# Stm32-mez.net
KiCad netlist of a schematic drawn in EAGLE
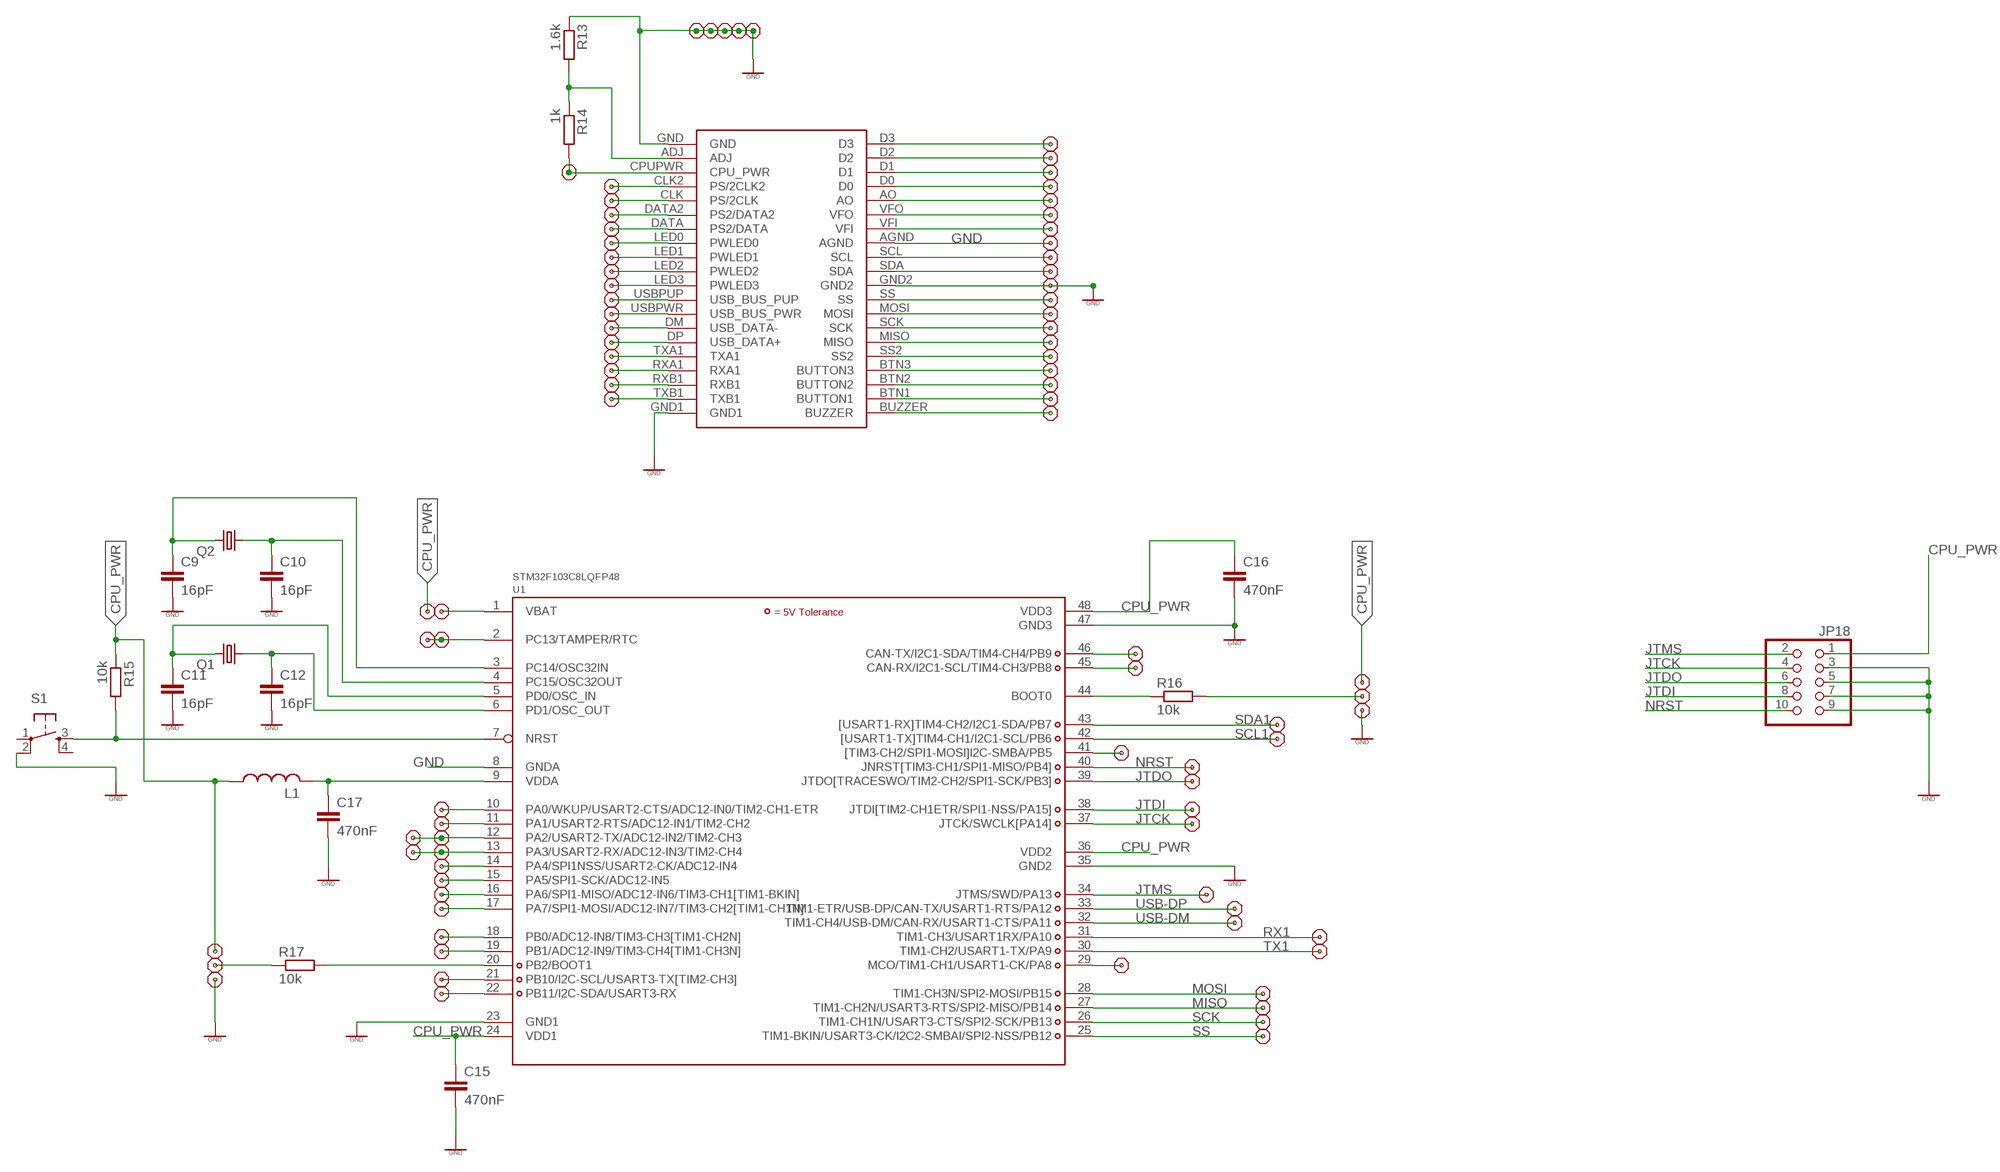
[diagram p0: schematic, sheet 1]

(export (version "E")
  (design (tool "Eeschema 10.0.6"))
  (components
    (comp (ref "C9")
      (value "16pF")
      (footprint "eagle-import:C1206")
      (libsource (lib "eagle-import") (part "C-EUC1206"))
    )
    (comp (ref "C10")
      (value "16pF")
      (footprint "eagle-import:C1206")
      (libsource (lib "eagle-import") (part "C-EUC1206"))
    )
    (comp (ref "C11")
      (value "16pF")
      (footprint "eagle-import:C1206")
      (libsource (lib "eagle-import") (part "C-EUC1206"))
    )
    (comp (ref "C12")
      (value "16pF")
      (footprint "eagle-import:C1206")
      (libsource (lib "eagle-import") (part "C-EUC1206"))
    )
    (comp (ref "C15")
      (value "470nF")
      (footprint "eagle-import:C1206")
      (libsource (lib "eagle-import") (part "C-EUC1206"))
    )
    (comp (ref "C16")
      (value "470nF")
      (footprint "eagle-import:C1206")
      (libsource (lib "eagle-import") (part "C-EUC1206"))
    )
    (comp (ref "C17")
      (value "470nF")
      (footprint "eagle-import:C1206")
      (libsource (lib "eagle-import") (part "C-EUC1206"))
    )
    (comp (ref "JP5")
      (value "PINHD-1X1PIN")
      (footprint "eagle-import:1X01")
      (libsource (lib "eagle-import") (part "PINHD-1X1PIN"))
    )
    (comp (ref "JP6")
      (value "PINHD-1X1PIN")
      (footprint "eagle-import:1X01")
      (libsource (lib "eagle-import") (part "PINHD-1X1PIN"))
    )
    (comp (ref "JP7")
      (value "PINHD-1X1PIN")
      (footprint "eagle-import:1X01")
      (libsource (lib "eagle-import") (part "PINHD-1X1PIN"))
    )
    (comp (ref "JP8")
      (value "PINHD-1X1PIN")
      (footprint "eagle-import:1X01")
      (libsource (lib "eagle-import") (part "PINHD-1X1PIN"))
    )
    (comp (ref "JP10")
      (value "PINHD-1X1PIN")
      (footprint "eagle-import:1X01")
      (libsource (lib "eagle-import") (part "PINHD-1X1PIN"))
    )
    (comp (ref "JP11")
      (value "PINHD-1X1PIN")
      (footprint "eagle-import:1X01")
      (libsource (lib "eagle-import") (part "PINHD-1X1PIN"))
    )
    (comp (ref "JP12")
      (value "PINHD-1X1PIN")
      (footprint "eagle-import:1X01")
      (libsource (lib "eagle-import") (part "PINHD-1X1PIN"))
    )
    (comp (ref "JP13")
      (value "PINHD-1X1PIN")
      (footprint "eagle-import:1X01")
      (libsource (lib "eagle-import") (part "PINHD-1X1PIN"))
    )
    (comp (ref "JP14")
      (value "PINHD-1X1PIN")
      (footprint "eagle-import:1X01")
      (libsource (lib "eagle-import") (part "PINHD-1X1PIN"))
    )
    (comp (ref "JP15")
      (value "PINHD-1X1PIN")
      (footprint "eagle-import:1X01")
      (libsource (lib "eagle-import") (part "PINHD-1X1PIN"))
    )
    (comp (ref "JP16")
      (value "PINHD-1X1PIN")
      (footprint "eagle-import:1X01")
      (libsource (lib "eagle-import") (part "PINHD-1X1PIN"))
    )
    (comp (ref "JP17")
      (value "PINHD-1X1PIN")
      (footprint "eagle-import:1X01")
      (libsource (lib "eagle-import") (part "PINHD-1X1PIN"))
    )
    (comp (ref "JP18")
      (value "PINHD-2X5")
      (footprint "eagle-import:2X05")
      (libsource (lib "eagle-import") (part "PINHD-2X5"))
    )
    (comp (ref "JP19")
      (value "PINHD-1X1PIN")
      (footprint "eagle-import:1X01")
      (libsource (lib "eagle-import") (part "PINHD-1X1PIN"))
    )
    (comp (ref "JP20")
      (value "PINHD-1X1PIN")
      (footprint "eagle-import:1X01")
      (libsource (lib "eagle-import") (part "PINHD-1X1PIN"))
    )
    (comp (ref "JP21")
      (value "PINHD-1X1PIN")
      (footprint "eagle-import:1X01")
      (libsource (lib "eagle-import") (part "PINHD-1X1PIN"))
    )
    (comp (ref "JP22")
      (value "PINHD-1X1PIN")
      (footprint "eagle-import:1X01")
      (libsource (lib "eagle-import") (part "PINHD-1X1PIN"))
    )
    (comp (ref "JP23")
      (value "PINHD-1X1PIN")
      (footprint "eagle-import:1X01")
      (libsource (lib "eagle-import") (part "PINHD-1X1PIN"))
    )
    (comp (ref "JP24")
      (value "PINHD-1X1PIN")
      (footprint "eagle-import:1X01")
      (libsource (lib "eagle-import") (part "PINHD-1X1PIN"))
    )
    (comp (ref "JP25")
      (value "PINHD-1X1PIN")
      (footprint "eagle-import:1X01")
      (libsource (lib "eagle-import") (part "PINHD-1X1PIN"))
    )
    (comp (ref "JP26")
      (value "PINHD-1X1PIN")
      (footprint "eagle-import:1X01")
      (libsource (lib "eagle-import") (part "PINHD-1X1PIN"))
    )
    (comp (ref "JP27")
      (value "PINHD-1X1PIN")
      (footprint "eagle-import:1X01")
      (libsource (lib "eagle-import") (part "PINHD-1X1PIN"))
    )
    (comp (ref "JP28")
      (value "PINHD-1X1PIN")
      (footprint "eagle-import:1X01")
      (libsource (lib "eagle-import") (part "PINHD-1X1PIN"))
    )
    (comp (ref "JP29")
      (value "PINHD-1X1PIN")
      (footprint "eagle-import:1X01")
      (libsource (lib "eagle-import") (part "PINHD-1X1PIN"))
    )
    (comp (ref "JP30")
      (value "PINHD-1X1PIN")
      (footprint "eagle-import:1X01")
      (libsource (lib "eagle-import") (part "PINHD-1X1PIN"))
    )
    (comp (ref "JP31")
      (value "PINHD-1X1PIN")
      (footprint "eagle-import:1X01")
      (libsource (lib "eagle-import") (part "PINHD-1X1PIN"))
    )
    (comp (ref "JP32")
      (value "PINHD-1X1PIN")
      (footprint "eagle-import:1X01")
      (libsource (lib "eagle-import") (part "PINHD-1X1PIN"))
    )
    (comp (ref "JP33")
      (value "PINHD-1X1PIN")
      (footprint "eagle-import:1X01")
      (libsource (lib "eagle-import") (part "PINHD-1X1PIN"))
    )
    (comp (ref "JP34")
      (value "PINHD-1X1PIN")
      (footprint "eagle-import:1X01")
      (libsource (lib "eagle-import") (part "PINHD-1X1PIN"))
    )
    (comp (ref "JP35")
      (value "PINHD-1X1PIN")
      (footprint "eagle-import:1X01")
      (libsource (lib "eagle-import") (part "PINHD-1X1PIN"))
    )
    (comp (ref "JP36")
      (value "PINHD-1X1PIN")
      (footprint "eagle-import:1X01")
      (libsource (lib "eagle-import") (part "PINHD-1X1PIN"))
    )
    (comp (ref "JP37")
      (value "PINHD-1X1PIN")
      (footprint "eagle-import:1X01")
      (libsource (lib "eagle-import") (part "PINHD-1X1PIN"))
    )
    (comp (ref "JP38")
      (value "PINHD-1X1PIN")
      (footprint "eagle-import:1X01")
      (libsource (lib "eagle-import") (part "PINHD-1X1PIN"))
    )
    (comp (ref "JP39")
      (value "PINHD-1X1PIN")
      (footprint "eagle-import:1X01")
      (libsource (lib "eagle-import") (part "PINHD-1X1PIN"))
    )
    (comp (ref "JP40")
      (value "PINHD-1X1PIN")
      (footprint "eagle-import:1X01")
      (libsource (lib "eagle-import") (part "PINHD-1X1PIN"))
    )
    (comp (ref "JP41")
      (value "PINHD-1X1PIN")
      (footprint "eagle-import:1X01")
      (libsource (lib "eagle-import") (part "PINHD-1X1PIN"))
    )
    (comp (ref "JP42")
      (value "PINHD-1X1PIN")
      (footprint "eagle-import:1X01")
      (libsource (lib "eagle-import") (part "PINHD-1X1PIN"))
    )
    (comp (ref "JP43")
      (value "PINHD-1X1PIN")
      (footprint "eagle-import:1X01")
      (libsource (lib "eagle-import") (part "PINHD-1X1PIN"))
    )
    (comp (ref "JP44")
      (value "PINHD-1X1PIN")
      (footprint "eagle-import:1X01")
      (libsource (lib "eagle-import") (part "PINHD-1X1PIN"))
    )
    (comp (ref "JP45")
      (value "PINHD-1X1PIN")
      (footprint "eagle-import:1X01")
      (libsource (lib "eagle-import") (part "PINHD-1X1PIN"))
    )
    (comp (ref "JP46")
      (value "PINHD-1X1PIN")
      (footprint "eagle-import:1X01")
      (libsource (lib "eagle-import") (part "PINHD-1X1PIN"))
    )
    (comp (ref "JP47")
      (value "PINHD-1X1PIN")
      (footprint "eagle-import:1X01")
      (libsource (lib "eagle-import") (part "PINHD-1X1PIN"))
    )
    (comp (ref "JP48")
      (value "PINHD-1X1PIN")
      (footprint "eagle-import:1X01")
      (libsource (lib "eagle-import") (part "PINHD-1X1PIN"))
    )
    (comp (ref "JP49")
      (value "PINHD-1X1PIN")
      (footprint "eagle-import:1X01")
      (libsource (lib "eagle-import") (part "PINHD-1X1PIN"))
    )
    (comp (ref "JP50")
      (value "PINHD-1X1PIN")
      (footprint "eagle-import:1X01")
      (libsource (lib "eagle-import") (part "PINHD-1X1PIN"))
    )
    (comp (ref "JP51")
      (value "PINHD-1X1PIN")
      (footprint "eagle-import:1X01")
      (libsource (lib "eagle-import") (part "PINHD-1X1PIN"))
    )
    (comp (ref "JP52")
      (value "PINHD-1X1PIN")
      (footprint "eagle-import:1X01")
      (libsource (lib "eagle-import") (part "PINHD-1X1PIN"))
    )
    (comp (ref "JP53")
      (value "PINHD-1X1PIN")
      (footprint "eagle-import:1X01")
      (libsource (lib "eagle-import") (part "PINHD-1X1PIN"))
    )
    (comp (ref "JP54")
      (value "PINHD-1X1PIN")
      (footprint "eagle-import:1X01")
      (libsource (lib "eagle-import") (part "PINHD-1X1PIN"))
    )
    (comp (ref "JP55")
      (value "PINHD-1X1PIN")
      (footprint "eagle-import:1X01")
      (libsource (lib "eagle-import") (part "PINHD-1X1PIN"))
    )
    (comp (ref "JP56")
      (value "PINHD-1X1PIN")
      (footprint "eagle-import:1X01")
      (libsource (lib "eagle-import") (part "PINHD-1X1PIN"))
    )
    (comp (ref "JP57")
      (value "PINHD-1X1PIN")
      (footprint "eagle-import:1X01")
      (libsource (lib "eagle-import") (part "PINHD-1X1PIN"))
    )
    (comp (ref "JP58")
      (value "PINHD-1X1PIN")
      (footprint "eagle-import:1X01")
      (libsource (lib "eagle-import") (part "PINHD-1X1PIN"))
    )
    (comp (ref "JP59")
      (value "PINHD-1X1PIN")
      (footprint "eagle-import:1X01")
      (libsource (lib "eagle-import") (part "PINHD-1X1PIN"))
    )
    (comp (ref "JP60")
      (value "PINHD-1X1PIN")
      (footprint "eagle-import:1X01")
      (libsource (lib "eagle-import") (part "PINHD-1X1PIN"))
    )
    (comp (ref "JP61")
      (value "PINHD-1X1PIN")
      (footprint "eagle-import:1X01")
      (libsource (lib "eagle-import") (part "PINHD-1X1PIN"))
    )
    (comp (ref "JP62")
      (value "PINHD-1X1PIN")
      (footprint "eagle-import:1X01")
      (libsource (lib "eagle-import") (part "PINHD-1X1PIN"))
    )
    (comp (ref "JP63")
      (value "PINHD-1X1PIN")
      (footprint "eagle-import:1X01")
      (libsource (lib "eagle-import") (part "PINHD-1X1PIN"))
    )
    (comp (ref "JP64")
      (value "PINHD-1X1PIN")
      (footprint "eagle-import:1X01")
      (libsource (lib "eagle-import") (part "PINHD-1X1PIN"))
    )
    (comp (ref "JP65")
      (value "PINHD-1X1PIN")
      (footprint "eagle-import:1X01")
      (libsource (lib "eagle-import") (part "PINHD-1X1PIN"))
    )
    (comp (ref "JP66")
      (value "PINHD-1X1PIN")
      (footprint "eagle-import:1X01")
      (libsource (lib "eagle-import") (part "PINHD-1X1PIN"))
    )
    (comp (ref "JP67")
      (value "PINHD-1X1PIN")
      (footprint "eagle-import:1X01")
      (libsource (lib "eagle-import") (part "PINHD-1X1PIN"))
    )
    (comp (ref "JP68")
      (value "PINHD-1X1PIN")
      (footprint "eagle-import:1X01")
      (libsource (lib "eagle-import") (part "PINHD-1X1PIN"))
    )
    (comp (ref "JP69")
      (value "PINHD-1X1PIN")
      (footprint "eagle-import:1X01")
      (libsource (lib "eagle-import") (part "PINHD-1X1PIN"))
    )
    (comp (ref "JP70")
      (value "PINHD-1X1PIN")
      (footprint "eagle-import:1X01")
      (libsource (lib "eagle-import") (part "PINHD-1X1PIN"))
    )
    (comp (ref "JP71")
      (value "PINHD-1X1PIN")
      (footprint "eagle-import:1X01")
      (libsource (lib "eagle-import") (part "PINHD-1X1PIN"))
    )
    (comp (ref "JP72")
      (value "PINHD-1X1PIN")
      (footprint "eagle-import:1X01")
      (libsource (lib "eagle-import") (part "PINHD-1X1PIN"))
    )
    (comp (ref "JP73")
      (value "PINHD-1X1PIN")
      (footprint "eagle-import:1X01")
      (libsource (lib "eagle-import") (part "PINHD-1X1PIN"))
    )
    (comp (ref "JP74")
      (value "PINHD-1X1PIN")
      (footprint "eagle-import:1X01")
      (libsource (lib "eagle-import") (part "PINHD-1X1PIN"))
    )
    (comp (ref "JP75")
      (value "PINHD-1X1PIN")
      (footprint "eagle-import:1X01")
      (libsource (lib "eagle-import") (part "PINHD-1X1PIN"))
    )
    (comp (ref "JP76")
      (value "PINHD-1X1PIN")
      (footprint "eagle-import:1X01")
      (libsource (lib "eagle-import") (part "PINHD-1X1PIN"))
    )
    (comp (ref "JP77")
      (value "PINHD-1X1PIN")
      (footprint "eagle-import:1X01")
      (libsource (lib "eagle-import") (part "PINHD-1X1PIN"))
    )
    (comp (ref "JP78")
      (value "PINHD-1X1PIN")
      (footprint "eagle-import:1X01")
      (libsource (lib "eagle-import") (part "PINHD-1X1PIN"))
    )
    (comp (ref "JP79")
      (value "PINHD-1X1PIN")
      (footprint "eagle-import:1X01")
      (libsource (lib "eagle-import") (part "PINHD-1X1PIN"))
    )
    (comp (ref "JP80")
      (value "PINHD-1X1PIN")
      (footprint "eagle-import:1X01")
      (libsource (lib "eagle-import") (part "PINHD-1X1PIN"))
    )
    (comp (ref "JP81")
      (value "PINHD-1X1PIN")
      (footprint "eagle-import:1X01")
      (libsource (lib "eagle-import") (part "PINHD-1X1PIN"))
    )
    (comp (ref "JP82")
      (value "PINHD-1X1PIN")
      (footprint "eagle-import:1X01")
      (libsource (lib "eagle-import") (part "PINHD-1X1PIN"))
    )
    (comp (ref "JP83")
      (value "PINHD-1X1PIN")
      (footprint "eagle-import:1X01")
      (libsource (lib "eagle-import") (part "PINHD-1X1PIN"))
    )
    (comp (ref "JP84")
      (value "PINHD-1X1PIN")
      (footprint "eagle-import:1X01")
      (libsource (lib "eagle-import") (part "PINHD-1X1PIN"))
    )
    (comp (ref "JP85")
      (value "PINHD-1X1PIN")
      (footprint "eagle-import:1X01")
      (libsource (lib "eagle-import") (part "PINHD-1X1PIN"))
    )
    (comp (ref "JP86")
      (value "PINHD-1X1PIN")
      (footprint "eagle-import:1X01")
      (libsource (lib "eagle-import") (part "PINHD-1X1PIN"))
    )
    (comp (ref "JP87")
      (value "PINHD-1X1PIN")
      (footprint "eagle-import:1X01")
      (libsource (lib "eagle-import") (part "PINHD-1X1PIN"))
    )
    (comp (ref "JP88")
      (value "PINHD-1X1PIN")
      (footprint "eagle-import:1X01")
      (libsource (lib "eagle-import") (part "PINHD-1X1PIN"))
    )
    (comp (ref "JP89")
      (value "PINHD-1X1PIN")
      (footprint "eagle-import:1X01")
      (libsource (lib "eagle-import") (part "PINHD-1X1PIN"))
    )
    (comp (ref "JP90")
      (value "PINHD-1X1PIN")
      (footprint "eagle-import:1X01")
      (libsource (lib "eagle-import") (part "PINHD-1X1PIN"))
    )
    (comp (ref "JP91")
      (value "PINHD-1X1PIN")
      (footprint "eagle-import:1X01")
      (libsource (lib "eagle-import") (part "PINHD-1X1PIN"))
    )
    (comp (ref "L1")
      (value "L-US0207/15")
      (footprint "eagle-import:0207_15")
      (libsource (lib "eagle-import") (part "L-US0207/15"))
    )
    (comp (ref "Q1")
      (value "CRYSTALHC49U-V")
      (footprint "eagle-import:HC49U-V")
      (libsource (lib "eagle-import") (part "CRYSTALHC49U-V"))
    )
    (comp (ref "Q2")
      (value "CRYSTALTC26H")
      (footprint "eagle-import:TC26H")
      (libsource (lib "eagle-import") (part "CRYSTALTC26H"))
    )
    (comp (ref "R13")
      (value "1.6k")
      (footprint "eagle-import:R1206")
      (libsource (lib "eagle-import") (part "R-EU_R1206"))
    )
    (comp (ref "R14")
      (value "1k")
      (footprint "eagle-import:R1206")
      (libsource (lib "eagle-import") (part "R-EU_R1206"))
    )
    (comp (ref "R15")
      (value "10k")
      (footprint "eagle-import:R1206")
      (libsource (lib "eagle-import") (part "R-EU_R1206"))
    )
    (comp (ref "R16")
      (value "10k")
      (footprint "eagle-import:R1206")
      (libsource (lib "eagle-import") (part "R-EU_R1206"))
    )
    (comp (ref "R17")
      (value "10k")
      (footprint "eagle-import:R1206")
      (libsource (lib "eagle-import") (part "R-EU_R1206"))
    )
    (comp (ref "S1")
      (value "TAC_SWITCHPTH")
      (footprint "eagle-import:TACTILE-PTH")
      (libsource (lib "eagle-import") (part "TAC_SWITCHPTH"))
    )
    (comp (ref "U$2")
      (value "CPU_CON")
      (footprint "eagle-import:CPU_SHIELD")
      (libsource (lib "eagle-import") (part "CPU_CON"))
    )
    (comp (ref "U1")
      (value "STM32F103C8LQFP48")
      (footprint "eagle-import:LQFP48")
      (libsource (lib "eagle-import") (part "STM32F103C8LQFP48"))
    )
  )
  (nets
    (net (code "1") (name "/JTCK") (class "Default")
      (node (ref "JP18") (pin "4") (pinfunction "4_4") (pintype "passive"))
      (node (ref "JP22") (pin "1") (pinfunction "1_1") (pintype "passive"))
      (node (ref "U1") (pin "37") (pinfunction "JTCK/SWCLK[PA14]_37") (pintype "bidirectional"))
    )
    (net (code "2") (name "/JTDI") (class "Default")
      (node (ref "JP18") (pin "8") (pinfunction "8_8") (pintype "passive"))
      (node (ref "JP21") (pin "1") (pinfunction "1_1") (pintype "passive"))
      (node (ref "U1") (pin "38") (pinfunction "JTDI[TIM2-CH1ETR/SPI1-NSS/PA15]_38") (pintype "bidirectional"))
    )
    (net (code "3") (name "/JTDO") (class "Default")
      (node (ref "JP18") (pin "6") (pinfunction "6_6") (pintype "passive"))
      (node (ref "JP20") (pin "1") (pinfunction "1_1") (pintype "passive"))
      (node (ref "U1") (pin "39") (pinfunction "JTDO[TRACESWO/TIM2-CH2/SPI1-SCK/PB3]_39") (pintype "bidirectional"))
    )
    (net (code "4") (name "/JTMS") (class "Default")
      (node (ref "JP18") (pin "2") (pinfunction "2_2") (pintype "passive"))
      (node (ref "JP26") (pin "1") (pinfunction "1_1") (pintype "passive"))
      (node (ref "U1") (pin "34") (pinfunction "JTMS/SWD/PA13_34") (pintype "bidirectional"))
    )
    (net (code "5") (name "/MISO") (class "Default")
      (node (ref "JP32") (pin "1") (pinfunction "1_1") (pintype "passive"))
      (node (ref "U1") (pin "27") (pinfunction "TIM1-CH2N/USART3-RTS/SPI2-MISO/PB14_27") (pintype "bidirectional"))
    )
    (net (code "6") (name "/MOSI") (class "Default")
      (node (ref "JP31") (pin "1") (pinfunction "1_1") (pintype "passive"))
      (node (ref "U1") (pin "28") (pinfunction "TIM1-CH3N/SPI2-MOSI/PB15_28") (pintype "bidirectional"))
    )
    (net (code "7") (name "/NRST") (class "Default")
      (node (ref "JP18") (pin "10") (pinfunction "10_10") (pintype "passive"))
      (node (ref "JP19") (pin "1") (pinfunction "1_1") (pintype "passive"))
      (node (ref "U1") (pin "40") (pinfunction "JNRST[TIM3-CH1/SPI1-MISO/PB4]_40") (pintype "bidirectional"))
    )
    (net (code "8") (name "/RX1") (class "Default")
      (node (ref "JP27") (pin "1") (pinfunction "1_1") (pintype "passive"))
      (node (ref "U1") (pin "31") (pinfunction "TIM1-CH3/USART1RX/PA10_31") (pintype "bidirectional"))
    )
    (net (code "9") (name "/SCK") (class "Default")
      (node (ref "JP33") (pin "1") (pinfunction "1_1") (pintype "passive"))
      (node (ref "U1") (pin "26") (pinfunction "TIM1-CH1N/USART3-CTS/SPI2-SCK/PB13_26") (pintype "bidirectional"))
    )
    (net (code "10") (name "/SCL1") (class "Default")
      (node (ref "JP36") (pin "1") (pinfunction "1_1") (pintype "passive"))
      (node (ref "U1") (pin "42") (pinfunction "[USART1-TX]TIM4-CH1/I2C1-SCL/PB6_42") (pintype "bidirectional"))
    )
    (net (code "11") (name "/SDA1") (class "Default")
      (node (ref "JP35") (pin "1") (pinfunction "1_1") (pintype "passive"))
      (node (ref "U1") (pin "43") (pinfunction "[USART1-RX]TIM4-CH2/I2C1-SDA/PB7_43") (pintype "bidirectional"))
    )
    (net (code "12") (name "/SS") (class "Default")
      (node (ref "JP34") (pin "1") (pinfunction "1_1") (pintype "passive"))
      (node (ref "U1") (pin "25") (pinfunction "TIM1-BKIN/USART3-CK/I2C2-SMBAI/SPI2-NSS/PB12_25") (pintype "bidirectional"))
    )
    (net (code "13") (name "/TX1") (class "Default")
      (node (ref "JP28") (pin "1") (pinfunction "1_1") (pintype "passive"))
      (node (ref "U1") (pin "30") (pinfunction "TIM1-CH2/USART1-TX/PA9_30") (pintype "bidirectional"))
    )
    (net (code "14") (name "/USB-DM") (class "Default")
      (node (ref "JP29") (pin "1") (pinfunction "1_1") (pintype "passive"))
      (node (ref "U1") (pin "32") (pinfunction "TIM1-CH4/USB-DM/CAN-RX/USART1-CTS/PA11_32") (pintype "bidirectional"))
    )
    (net (code "15") (name "/USB-DP") (class "Default")
      (node (ref "JP30") (pin "1") (pinfunction "1_1") (pintype "passive"))
      (node (ref "U1") (pin "33") (pinfunction "TIM1-ETR/USB-DP/CAN-TX/USART1-RTS/PA12_33") (pintype "bidirectional"))
    )
    (net (code "16") (name "CPU_PWR") (class "Default")
      (node (ref "C15") (pin "1") (pinfunction "1_1") (pintype "passive"))
      (node (ref "C16") (pin "1") (pinfunction "1_1") (pintype "passive"))
      (node (ref "JP16") (pin "1") (pinfunction "1_1") (pintype "passive"))
      (node (ref "JP18") (pin "1") (pinfunction "1_1") (pintype "passive"))
      (node (ref "JP24") (pin "1") (pinfunction "1_1") (pintype "passive"))
      (node (ref "JP5") (pin "1") (pinfunction "1_1") (pintype "passive"))
      (node (ref "JP54") (pin "1") (pinfunction "1_1") (pintype "passive"))
      (node (ref "L1") (pin "1") (pinfunction "1_1") (pintype "passive"))
      (node (ref "R14") (pin "2") (pinfunction "2_2") (pintype "passive"))
      (node (ref "R15") (pin "1") (pinfunction "1_1") (pintype "passive"))
      (node (ref "U$2") (pin "CPUPWR") (pinfunction "CPU_PWR_CPUPWR") (pintype "bidirectional"))
      (node (ref "U1") (pin "24") (pinfunction "VDD1_24") (pintype "power_in"))
      (node (ref "U1") (pin "36") (pinfunction "VDD2_36") (pintype "power_in"))
      (node (ref "U1") (pin "48") (pinfunction "VDD3_48") (pintype "power_in"))
    )
    (net (code "17") (name "GND") (class "Default")
      (node (ref "C10") (pin "2") (pinfunction "2_2") (pintype "passive"))
      (node (ref "C11") (pin "2") (pinfunction "2_2") (pintype "passive"))
      (node (ref "C12") (pin "2") (pinfunction "2_2") (pintype "passive"))
      (node (ref "C15") (pin "2") (pinfunction "2_2") (pintype "passive"))
      (node (ref "C16") (pin "2") (pinfunction "2_2") (pintype "passive"))
      (node (ref "C17") (pin "2") (pinfunction "2_2") (pintype "passive"))
      (node (ref "C9") (pin "2") (pinfunction "2_2") (pintype "passive"))
      (node (ref "JP10") (pin "1") (pinfunction "1_1") (pintype "passive"))
      (node (ref "JP11") (pin "1") (pinfunction "1_1") (pintype "passive"))
      (node (ref "JP12") (pin "1") (pinfunction "1_1") (pintype "passive"))
      (node (ref "JP13") (pin "1") (pinfunction "1_1") (pintype "passive"))
      (node (ref "JP14") (pin "1") (pinfunction "1_1") (pintype "passive"))
      (node (ref "JP18") (pin "3") (pinfunction "3_3") (pintype "passive"))
      (node (ref "JP18") (pin "5") (pinfunction "5_5") (pintype "passive"))
      (node (ref "JP18") (pin "7") (pinfunction "7_7") (pintype "passive"))
      (node (ref "JP18") (pin "9") (pinfunction "9_9") (pintype "passive"))
      (node (ref "JP25") (pin "1") (pinfunction "1_1") (pintype "passive"))
      (node (ref "JP55") (pin "1") (pinfunction "1_1") (pintype "passive"))
      (node (ref "JP90") (pin "1") (pinfunction "1_1") (pintype "passive"))
      (node (ref "JP91") (pin "1") (pinfunction "1_1") (pintype "passive"))
      (node (ref "R13") (pin "1") (pinfunction "1_1") (pintype "passive"))
      (node (ref "S1") (pin "2") (pinfunction "2_2") (pintype "passive"))
      (node (ref "U$2") (pin "AGND") (pinfunction "AGND_AGND") (pintype "bidirectional"))
      (node (ref "U$2") (pin "GND") (pinfunction "GND_GND") (pintype "bidirectional"))
      (node (ref "U$2") (pin "GND1") (pinfunction "GND1_GND1") (pintype "bidirectional"))
      (node (ref "U$2") (pin "GND2") (pinfunction "GND2_GND2") (pintype "bidirectional"))
      (node (ref "U1") (pin "23") (pinfunction "GND1_23") (pintype "power_in"))
      (node (ref "U1") (pin "35") (pinfunction "GND2_35") (pintype "power_in"))
      (node (ref "U1") (pin "47") (pinfunction "GND3_47") (pintype "power_in"))
      (node (ref "U1") (pin "8") (pinfunction "GNDA_8") (pintype "power_in"))
    )
    (net (code "18") (name "Net-(JP23-Pad1)") (class "Default")
      (node (ref "JP23") (pin "1") (pinfunction "1_1") (pintype "passive"))
      (node (ref "R16") (pin "2") (pinfunction "2_2") (pintype "passive"))
    )
    (net (code "19") (name "Net-(JP51-Pad1)") (class "Default")
      (node (ref "JP51") (pin "1") (pinfunction "1_1") (pintype "passive"))
      (node (ref "R17") (pin "1") (pinfunction "1_1") (pintype "passive"))
    )
    (net (code "20") (name "Net-(JP56-Pad1)") (class "Default")
      (node (ref "JP56") (pin "1") (pinfunction "1_1") (pintype "passive"))
      (node (ref "U$2") (pin "BUZZER") (pinfunction "BUZZER_BUZZER") (pintype "bidirectional"))
    )
    (net (code "21") (name "Net-(JP60-Pad1)") (class "Default")
      (node (ref "JP60") (pin "1") (pinfunction "1_1") (pintype "passive"))
      (node (ref "U$2") (pin "SS2") (pinfunction "SS2_SS2") (pintype "bidirectional"))
    )
    (net (code "22") (name "Net-(JP61-Pad1)") (class "Default")
      (node (ref "JP61") (pin "1") (pinfunction "1_1") (pintype "passive"))
      (node (ref "U$2") (pin "MISO") (pinfunction "MISO_MISO") (pintype "bidirectional"))
    )
    (net (code "23") (name "Net-(JP62-Pad1)") (class "Default")
      (node (ref "JP62") (pin "1") (pinfunction "1_1") (pintype "passive"))
      (node (ref "U$2") (pin "SCK") (pinfunction "SCK_SCK") (pintype "bidirectional"))
    )
    (net (code "24") (name "Net-(JP63-Pad1)") (class "Default")
      (node (ref "JP63") (pin "1") (pinfunction "1_1") (pintype "passive"))
      (node (ref "U$2") (pin "MOSI") (pinfunction "MOSI_MOSI") (pintype "bidirectional"))
    )
    (net (code "25") (name "Net-(JP64-Pad1)") (class "Default")
      (node (ref "JP64") (pin "1") (pinfunction "1_1") (pintype "passive"))
      (node (ref "U$2") (pin "SS") (pinfunction "SS_SS") (pintype "bidirectional"))
    )
    (net (code "26") (name "Net-(JP65-Pad1)") (class "Default")
      (node (ref "JP65") (pin "1") (pinfunction "1_1") (pintype "passive"))
      (node (ref "U$2") (pin "SDA") (pinfunction "SDA_SDA") (pintype "bidirectional"))
    )
    (net (code "27") (name "Net-(JP66-Pad1)") (class "Default")
      (node (ref "JP66") (pin "1") (pinfunction "1_1") (pintype "passive"))
      (node (ref "U$2") (pin "SCL") (pinfunction "SCL_SCL") (pintype "bidirectional"))
    )
    (net (code "28") (name "Net-(JP67-Pad1)") (class "Default")
      (node (ref "JP67") (pin "1") (pinfunction "1_1") (pintype "passive"))
      (node (ref "U$2") (pin "VFI") (pinfunction "VFI_VFI") (pintype "bidirectional"))
    )
    (net (code "29") (name "Net-(JP68-Pad1)") (class "Default")
      (node (ref "JP68") (pin "1") (pinfunction "1_1") (pintype "passive"))
      (node (ref "U$2") (pin "VFO") (pinfunction "VFO_VFO") (pintype "bidirectional"))
    )
    (net (code "30") (name "Net-(JP69-Pad1)") (class "Default")
      (node (ref "JP69") (pin "1") (pinfunction "1_1") (pintype "passive"))
      (node (ref "U$2") (pin "AO") (pinfunction "AO_AO") (pintype "bidirectional"))
    )
    (net (code "31") (name "Net-(JP70-Pad1)") (class "Default")
      (node (ref "JP70") (pin "1") (pinfunction "1_1") (pintype "passive"))
      (node (ref "U$2") (pin "D0") (pinfunction "D0_D0") (pintype "bidirectional"))
    )
    (net (code "32") (name "Net-(JP71-Pad1)") (class "Default")
      (node (ref "JP71") (pin "1") (pinfunction "1_1") (pintype "passive"))
      (node (ref "U$2") (pin "D1") (pinfunction "D1_D1") (pintype "bidirectional"))
    )
    (net (code "33") (name "Net-(JP72-Pad1)") (class "Default")
      (node (ref "JP72") (pin "1") (pinfunction "1_1") (pintype "passive"))
      (node (ref "U$2") (pin "D2") (pinfunction "D2_D2") (pintype "bidirectional"))
    )
    (net (code "34") (name "Net-(JP73-Pad1)") (class "Default")
      (node (ref "JP73") (pin "1") (pinfunction "1_1") (pintype "passive"))
      (node (ref "U$2") (pin "D3") (pinfunction "D3_D3") (pintype "bidirectional"))
    )
    (net (code "35") (name "Net-(JP74-Pad1)") (class "Default")
      (node (ref "JP74") (pin "1") (pinfunction "1_1") (pintype "passive"))
      (node (ref "U$2") (pin "TXB1") (pinfunction "TXB1_TXB1") (pintype "bidirectional"))
    )
    (net (code "36") (name "Net-(JP75-Pad1)") (class "Default")
      (node (ref "JP75") (pin "1") (pinfunction "1_1") (pintype "passive"))
      (node (ref "U$2") (pin "RXB1") (pinfunction "RXB1_RXB1") (pintype "bidirectional"))
    )
    (net (code "37") (name "Net-(JP76-Pad1)") (class "Default")
      (node (ref "JP76") (pin "1") (pinfunction "1_1") (pintype "passive"))
      (node (ref "U$2") (pin "RXA1") (pinfunction "RXA1_RXA1") (pintype "bidirectional"))
    )
    (net (code "38") (name "Net-(JP77-Pad1)") (class "Default")
      (node (ref "JP77") (pin "1") (pinfunction "1_1") (pintype "passive"))
      (node (ref "U$2") (pin "TXA1") (pinfunction "TXA1_TXA1") (pintype "bidirectional"))
    )
    (net (code "39") (name "Net-(R13-Pad2)") (class "Default")
      (node (ref "R13") (pin "2") (pinfunction "2_2") (pintype "passive"))
      (node (ref "R14") (pin "1") (pinfunction "1_1") (pintype "passive"))
      (node (ref "U$2") (pin "ADJ") (pinfunction "ADJ_ADJ") (pintype "bidirectional"))
    )
    (net (code "40") (name "Net-(U$2-BUTTON1)") (class "Default")
      (node (ref "JP57") (pin "1") (pinfunction "1_1") (pintype "passive"))
      (node (ref "U$2") (pin "BTN1") (pinfunction "BUTTON1_BTN1") (pintype "bidirectional"))
    )
    (net (code "41") (name "Net-(U$2-BUTTON2)") (class "Default")
      (node (ref "JP58") (pin "1") (pinfunction "1_1") (pintype "passive"))
      (node (ref "U$2") (pin "BTN2") (pinfunction "BUTTON2_BTN2") (pintype "bidirectional"))
    )
    (net (code "42") (name "Net-(U$2-BUTTON3)") (class "Default")
      (node (ref "JP59") (pin "1") (pinfunction "1_1") (pintype "passive"))
      (node (ref "U$2") (pin "BTN3") (pinfunction "BUTTON3_BTN3") (pintype "bidirectional"))
    )
    (net (code "43") (name "Net-(U$2-PS2{slash}DATA)") (class "Default")
      (node (ref "JP86") (pin "1") (pinfunction "1_1") (pintype "passive"))
      (node (ref "U$2") (pin "DATA") (pinfunction "PS2/DATA_DATA") (pintype "bidirectional"))
    )
    (net (code "44") (name "Net-(U$2-PS2{slash}DATA2)") (class "Default")
      (node (ref "JP87") (pin "1") (pinfunction "1_1") (pintype "passive"))
      (node (ref "U$2") (pin "DATA2") (pinfunction "PS2/DATA2_DATA2") (pintype "bidirectional"))
    )
    (net (code "45") (name "Net-(U$2-PS{slash}2CLK)") (class "Default")
      (node (ref "JP88") (pin "1") (pinfunction "1_1") (pintype "passive"))
      (node (ref "U$2") (pin "CLK") (pinfunction "PS/2CLK_CLK") (pintype "bidirectional"))
    )
    (net (code "46") (name "Net-(U$2-PS{slash}2CLK2)") (class "Default")
      (node (ref "JP89") (pin "1") (pinfunction "1_1") (pintype "passive"))
      (node (ref "U$2") (pin "CLK2") (pinfunction "PS/2CLK2_CLK2") (pintype "bidirectional"))
    )
    (net (code "47") (name "Net-(U$2-PWLED0)") (class "Default")
      (node (ref "JP85") (pin "1") (pinfunction "1_1") (pintype "passive"))
      (node (ref "U$2") (pin "LED0") (pinfunction "PWLED0_LED0") (pintype "bidirectional"))
    )
    (net (code "48") (name "Net-(U$2-PWLED1)") (class "Default")
      (node (ref "JP84") (pin "1") (pinfunction "1_1") (pintype "passive"))
      (node (ref "U$2") (pin "LED1") (pinfunction "PWLED1_LED1") (pintype "bidirectional"))
    )
    (net (code "49") (name "Net-(U$2-PWLED2)") (class "Default")
      (node (ref "JP83") (pin "1") (pinfunction "1_1") (pintype "passive"))
      (node (ref "U$2") (pin "LED2") (pinfunction "PWLED2_LED2") (pintype "bidirectional"))
    )
    (net (code "50") (name "Net-(U$2-PWLED3)") (class "Default")
      (node (ref "JP82") (pin "1") (pinfunction "1_1") (pintype "passive"))
      (node (ref "U$2") (pin "LED3") (pinfunction "PWLED3_LED3") (pintype "bidirectional"))
    )
    (net (code "51") (name "Net-(U$2-USB_BUS_PUP)") (class "Default")
      (node (ref "JP81") (pin "1") (pinfunction "1_1") (pintype "passive"))
      (node (ref "U$2") (pin "USBPUP") (pinfunction "USB_BUS_PUP_USBPUP") (pintype "bidirectional"))
    )
    (net (code "52") (name "Net-(U$2-USB_BUS_PWR)") (class "Default")
      (node (ref "JP80") (pin "1") (pinfunction "1_1") (pintype "passive"))
      (node (ref "U$2") (pin "USBPWR") (pinfunction "USB_BUS_PWR_USBPWR") (pintype "bidirectional"))
    )
    (net (code "53") (name "Net-(U$2-USB_DATA+)") (class "Default")
      (node (ref "JP78") (pin "1") (pinfunction "1_1") (pintype "passive"))
      (node (ref "U$2") (pin "DP") (pinfunction "USB_DATA+_DP") (pintype "bidirectional"))
    )
    (net (code "54") (name "Net-(U$2-USB_DATA-)") (class "Default")
      (node (ref "JP79") (pin "1") (pinfunction "1_1") (pintype "passive"))
      (node (ref "U$2") (pin "DM") (pinfunction "USB_DATA-_DM") (pintype "bidirectional"))
    )
    (net (code "55") (name "Net-(U1-BOOT0)") (class "Default")
      (node (ref "R16") (pin "1") (pinfunction "1_1") (pintype "passive"))
      (node (ref "U1") (pin "44") (pinfunction "BOOT0_44") (pintype "bidirectional"))
    )
    (net (code "56") (name "Net-(U1-CAN-RX{slash}I2C1-SCL{slash}TIM4-CH3{slash}PB8)") (class "Default")
      (node (ref "JP37") (pin "1") (pinfunction "1_1") (pintype "passive"))
      (node (ref "U1") (pin "45") (pinfunction "CAN-RX/I2C1-SCL/TIM4-CH3/PB8_45") (pintype "bidirectional"))
    )
    (net (code "57") (name "Net-(U1-CAN-TX{slash}I2C1-SDA{slash}TIM4-CH4{slash}PB9)") (class "Default")
      (node (ref "JP38") (pin "1") (pinfunction "1_1") (pintype "passive"))
      (node (ref "U1") (pin "46") (pinfunction "CAN-TX/I2C1-SDA/TIM4-CH4/PB9_46") (pintype "bidirectional"))
    )
    (net (code "58") (name "Net-(U1-MCO{slash}TIM1-CH1{slash}USART1-CK{slash}PA8)") (class "Default")
      (node (ref "JP40") (pin "1") (pinfunction "1_1") (pintype "passive"))
      (node (ref "U1") (pin "29") (pinfunction "MCO/TIM1-CH1/USART1-CK/PA8_29") (pintype "bidirectional"))
    )
    (net (code "59") (name "Net-(U1-NRST)") (class "Default")
      (node (ref "R15") (pin "2") (pinfunction "2_2") (pintype "passive"))
      (node (ref "S1") (pin "3") (pinfunction "3_3") (pintype "passive"))
      (node (ref "U1") (pin "7") (pinfunction "NRST_7") (pintype "bidirectional"))
    )
    (net (code "60") (name "Net-(U1-PA0{slash}WKUP{slash}USART2-CTS{slash}ADC12-IN0{slash}TIM2-CH1-ETR)") (class "Default")
      (node (ref "JP41") (pin "1") (pinfunction "1_1") (pintype "passive"))
      (node (ref "U1") (pin "10") (pinfunction "PA0/WKUP/USART2-CTS/ADC12-IN0/TIM2-CH1-ETR_10") (pintype "bidirectional"))
    )
    (net (code "61") (name "Net-(U1-PA1{slash}USART2-RTS{slash}ADC12-IN1{slash}TIM2-CH2)") (class "Default")
      (node (ref "JP43") (pin "1") (pinfunction "1_1") (pintype "passive"))
      (node (ref "U1") (pin "11") (pinfunction "PA1/USART2-RTS/ADC12-IN1/TIM2-CH2_11") (pintype "bidirectional"))
    )
    (net (code "62") (name "Net-(U1-PA2{slash}USART2-TX{slash}ADC12-IN2{slash}TIM2-CH3)") (class "Default")
      (node (ref "JP42") (pin "1") (pinfunction "1_1") (pintype "passive"))
      (node (ref "JP6") (pin "1") (pinfunction "1_1") (pintype "passive"))
      (node (ref "U1") (pin "12") (pinfunction "PA2/USART2-TX/ADC12-IN2/TIM2-CH3_12") (pintype "bidirectional"))
    )
    (net (code "63") (name "Net-(U1-PA3{slash}USART2-RX{slash}ADC12-IN3{slash}TIM2-CH4)") (class "Default")
      (node (ref "JP44") (pin "1") (pinfunction "1_1") (pintype "passive"))
      (node (ref "JP7") (pin "1") (pinfunction "1_1") (pintype "passive"))
      (node (ref "U1") (pin "13") (pinfunction "PA3/USART2-RX/ADC12-IN3/TIM2-CH4_13") (pintype "bidirectional"))
    )
    (net (code "64") (name "Net-(U1-PA4{slash}SPI1NSS{slash}USART2-CK{slash}ADC12-IN4)") (class "Default")
      (node (ref "JP45") (pin "1") (pinfunction "1_1") (pintype "passive"))
      (node (ref "U1") (pin "14") (pinfunction "PA4/SPI1NSS/USART2-CK/ADC12-IN4_14") (pintype "bidirectional"))
    )
    (net (code "65") (name "Net-(U1-PA5{slash}SPI1-SCK{slash}ADC12-IN5)") (class "Default")
      (node (ref "JP46") (pin "1") (pinfunction "1_1") (pintype "passive"))
      (node (ref "U1") (pin "15") (pinfunction "PA5/SPI1-SCK/ADC12-IN5_15") (pintype "bidirectional"))
    )
    (net (code "66") (name "Net-(U1-PA6{slash}SPI1-MISO{slash}ADC12-IN6{slash}TIM3-CH1[TIM1-BKIN])") (class "Default")
      (node (ref "JP47") (pin "1") (pinfunction "1_1") (pintype "passive"))
      (node (ref "U1") (pin "16") (pinfunction "PA6/SPI1-MISO/ADC12-IN6/TIM3-CH1[TIM1-BKIN]_16") (pintype "bidirectional"))
    )
    (net (code "67") (name "Net-(U1-PA7{slash}SPI1-MOSI{slash}ADC12-IN7{slash}TIM3-CH2[TIM1-CH1N])") (class "Default")
      (node (ref "JP48") (pin "1") (pinfunction "1_1") (pintype "passive"))
      (node (ref "U1") (pin "17") (pinfunction "PA7/SPI1-MOSI/ADC12-IN7/TIM3-CH2[TIM1-CH1N]_17") (pintype "bidirectional"))
    )
    (net (code "68") (name "Net-(U1-PB0{slash}ADC12-IN8{slash}TIM3-CH3[TIM1-CH2N])") (class "Default")
      (node (ref "JP49") (pin "1") (pinfunction "1_1") (pintype "passive"))
      (node (ref "U1") (pin "18") (pinfunction "PB0/ADC12-IN8/TIM3-CH3[TIM1-CH2N]_18") (pintype "bidirectional"))
    )
    (net (code "69") (name "Net-(U1-PB1{slash}ADC12-IN9{slash}TIM3-CH4[TIM1-CH3N])") (class "Default")
      (node (ref "JP50") (pin "1") (pinfunction "1_1") (pintype "passive"))
      (node (ref "U1") (pin "19") (pinfunction "PB1/ADC12-IN9/TIM3-CH4[TIM1-CH3N]_19") (pintype "bidirectional"))
    )
    (net (code "70") (name "Net-(U1-PB2{slash}BOOT1)") (class "Default")
      (node (ref "R17") (pin "2") (pinfunction "2_2") (pintype "passive"))
      (node (ref "U1") (pin "20") (pinfunction "PB2/BOOT1_20") (pintype "bidirectional"))
    )
    (net (code "71") (name "Net-(U1-PB10{slash}I2C-SCL{slash}USART3-TX[TIM2-CH3])") (class "Default")
      (node (ref "JP52") (pin "1") (pinfunction "1_1") (pintype "passive"))
      (node (ref "U1") (pin "21") (pinfunction "PB10/I2C-SCL/USART3-TX[TIM2-CH3]_21") (pintype "bidirectional"))
    )
    (net (code "72") (name "Net-(U1-PB11{slash}I2C-SDA{slash}USART3-RX)") (class "Default")
      (node (ref "JP53") (pin "1") (pinfunction "1_1") (pintype "passive"))
      (node (ref "U1") (pin "22") (pinfunction "PB11/I2C-SDA/USART3-RX_22") (pintype "bidirectional"))
    )
    (net (code "73") (name "Net-(U1-PC13{slash}TAMPER{slash}RTC)") (class "Default")
      (node (ref "JP17") (pin "1") (pinfunction "1_1") (pintype "passive"))
      (node (ref "JP8") (pin "1") (pinfunction "1_1") (pintype "passive"))
      (node (ref "U1") (pin "2") (pinfunction "PC13/TAMPER/RTC_2") (pintype "bidirectional"))
    )
    (net (code "74") (name "Net-(U1-PC14{slash}OSC32IN)") (class "Default")
      (node (ref "C9") (pin "1") (pinfunction "1_1") (pintype "passive"))
      (node (ref "Q2") (pin "2") (pinfunction "2_2") (pintype "passive"))
      (node (ref "U1") (pin "3") (pinfunction "PC14/OSC32IN_3") (pintype "bidirectional"))
    )
    (net (code "75") (name "Net-(U1-PC15{slash}OSC32OUT)") (class "Default")
      (node (ref "C10") (pin "1") (pinfunction "1_1") (pintype "passive"))
      (node (ref "Q2") (pin "1") (pinfunction "1_1") (pintype "passive"))
      (node (ref "U1") (pin "4") (pinfunction "PC15/OSC32OUT_4") (pintype "bidirectional"))
    )
    (net (code "76") (name "Net-(U1-PD0{slash}OSC_IN)") (class "Default")
      (node (ref "C11") (pin "1") (pinfunction "1_1") (pintype "passive"))
      (node (ref "Q1") (pin "2") (pinfunction "2_2") (pintype "passive"))
      (node (ref "U1") (pin "5") (pinfunction "PD0/OSC_IN_5") (pintype "bidirectional"))
    )
    (net (code "77") (name "Net-(U1-PD1{slash}OSC_OUT)") (class "Default")
      (node (ref "C12") (pin "1") (pinfunction "1_1") (pintype "passive"))
      (node (ref "Q1") (pin "1") (pinfunction "1_1") (pintype "passive"))
      (node (ref "U1") (pin "6") (pinfunction "PD1/OSC_OUT_6") (pintype "bidirectional"))
    )
    (net (code "78") (name "Net-(U1-VBAT)") (class "Default")
      (node (ref "JP15") (pin "1") (pinfunction "1_1") (pintype "passive"))
      (node (ref "U1") (pin "1") (pinfunction "VBAT_1") (pintype "power_in"))
    )
    (net (code "79") (name "Net-(U1-VDDA)") (class "Default")
      (node (ref "C17") (pin "1") (pinfunction "1_1") (pintype "passive"))
      (node (ref "L1") (pin "2") (pinfunction "2_2") (pintype "passive"))
      (node (ref "U1") (pin "9") (pinfunction "VDDA_9") (pintype "power_in"))
    )
    (net (code "80") (name "Net-(U1-[TIM3-CH2{slash}SPI1-MOSI]I2C-SMBA{slash}PB5)") (class "Default")
      (node (ref "JP39") (pin "1") (pinfunction "1_1") (pintype "passive"))
      (node (ref "U1") (pin "41") (pinfunction "[TIM3-CH2/SPI1-MOSI]I2C-SMBA/PB5_41") (pintype "bidirectional"))
    )
    (net (code "81") (name "unconnected-(S1-Pad1)") (class "Default")
      (node (ref "S1") (pin "1") (pinfunction "1_1") (pintype "passive"))
    )
    (net (code "82") (name "unconnected-(S1-Pad4)") (class "Default")
      (node (ref "S1") (pin "4") (pinfunction "4_4") (pintype "passive"))
    )
  )
)
